# BackUp_uC.net
KiCad netlist of a schematic drawn in Altium Designer
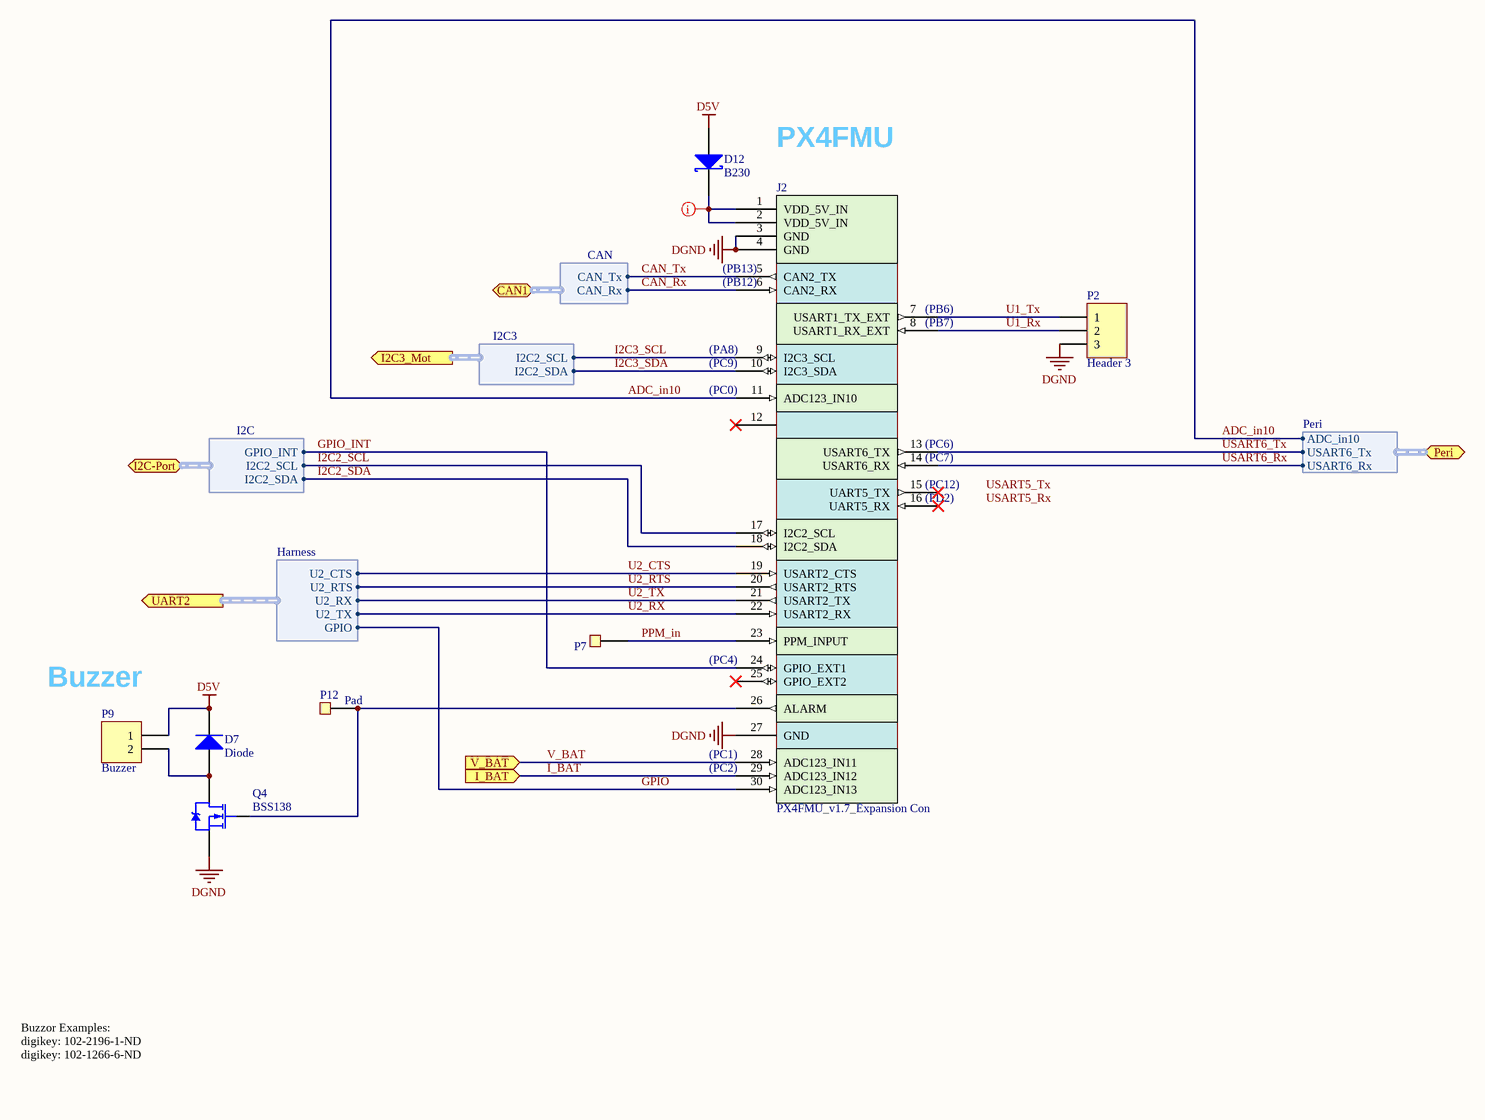
[diagram p0: BackUp_uC.SchDoc]

(export (version "E")
  (design (tool "Eeschema 10.0.6"))
  (components
    (comp (ref "D7")
      (value "Diode")
      (footprint "Mini MELF - SOD-80 -N")
      (description "Default Diode")
      (libsource (lib "IDSC std generic parts ") (part "Diode"))
    )
    (comp (ref "D12")
      (value "B230")
      (footprint "Diode SMB DO-214aa -N")
      (description "Schottky Diode")
      (libsource (lib "IDSC std generic parts ") (part "Diode  Schottky"))
    )
    (comp (ref "J2")
      (value "PX4FMU_v1.7_Expansion Con")
      (footprint "PX4FMU_v1.7_module_sicket")
      (description "J2 / J3")
      (libsource (lib "IDSC_PX4_modules") (part "PX4FMU_v1.7_Expansion Con_1"))
    )
    (comp (ref "P2")
      (value "Header 3")
      (footprint "HDR1X3")
      (description "Header, 3-Pin")
      (libsource (lib "IDSC std connectors") (part "Header 3"))
    )
    (comp (ref "P7")
      (value "Pad")
      (footprint "PIN1 style 2")
      (description "Single Pad or Testpoint")
      (libsource (lib "IDSC std connectors") (part "Pad"))
    )
    (comp (ref "P9")
      (value "Buzzer")
      (footprint "HDR1X2")
      (description "Header, 2-Pin")
      (libsource (lib "IDSC std connectors") (part "Header 2"))
    )
    (comp (ref "P12")
      (value "Pad")
      (footprint "Pad_0603")
      (description "Single Pad or Testpoint")
      (libsource (lib "IDSC std connectors") (part "Pad"))
    )
    (comp (ref "Q4")
      (value "BSS138")
      (footprint "SOT23-N")
      (description "N-Channel MOSFET")
      (libsource (lib "IDSC std generic parts ") (part "MOSFET-N2"))
    )
  )
  (nets
    (net (code "6") (name "/ADC_in10") (class "Default")
      (node (ref "J2") (pin "11") (pinfunction "ADC123_IN10_11") (pintype "input"))
    )
    (net (code "7") (name "/CAN_Rx") (class "Default")
      (node (ref "J2") (pin "6") (pinfunction "CAN2_RX_6") (pintype "input"))
    )
    (net (code "8") (name "/CAN_Tx") (class "Default")
      (node (ref "J2") (pin "5") (pinfunction "CAN2_TX_5") (pintype "output"))
    )
    (net (code "9") (name "/GPIO") (class "Default")
      (node (ref "J2") (pin "30") (pinfunction "ADC123_IN13_30") (pintype "input"))
    )
    (net (code "10") (name "/GPIO_INT") (class "Default")
      (node (ref "J2") (pin "24") (pinfunction "GPIO_EXT1_24") (pintype "bidirectional"))
    )
    (net (code "11") (name "/I2C2_SCL") (class "Default")
      (node (ref "J2") (pin "17") (pinfunction "I2C2_SCL_17") (pintype "bidirectional"))
    )
    (net (code "12") (name "/I2C2_SDA") (class "Default")
      (node (ref "J2") (pin "18") (pinfunction "I2C2_SDA_18") (pintype "bidirectional"))
    )
    (net (code "13") (name "/I2C3_SCL") (class "Default")
      (node (ref "J2") (pin "9") (pinfunction "I2C3_SCL_9") (pintype "bidirectional"))
    )
    (net (code "14") (name "/I2C3_SDA") (class "Default")
      (node (ref "J2") (pin "10") (pinfunction "I2C3_SDA_10") (pintype "bidirectional"))
    )
    (net (code "15") (name "/I_BAT") (class "Default")
      (node (ref "J2") (pin "29") (pinfunction "ADC123_IN12_29") (pintype "input"))
    )
    (net (code "16") (name "/PPM_in") (class "Default")
      (node (ref "J2") (pin "23") (pinfunction "PPM_INPUT_23") (pintype "input"))
      (node (ref "P7") (pin "1") (pinfunction "1_1") (pintype "passive"))
    )
    (net (code "17") (name "/U1_Rx") (class "Default")
      (node (ref "J2") (pin "8") (pinfunction "USART1_RX_EXT_8") (pintype "input"))
      (node (ref "P2") (pin "2") (pinfunction "2_2") (pintype "passive"))
    )
    (net (code "18") (name "/U1_Tx") (class "Default")
      (node (ref "J2") (pin "7") (pinfunction "USART1_TX_EXT_7") (pintype "output"))
      (node (ref "P2") (pin "1") (pinfunction "1_1") (pintype "passive"))
    )
    (net (code "19") (name "/U2_CTS") (class "Default")
      (node (ref "J2") (pin "19") (pinfunction "USART2_CTS_19") (pintype "input"))
    )
    (net (code "20") (name "/U2_RTS") (class "Default")
      (node (ref "J2") (pin "20") (pinfunction "USART2_RTS_20") (pintype "output"))
    )
    (net (code "21") (name "/U2_RX") (class "Default")
      (node (ref "J2") (pin "22") (pinfunction "USART2_RX_22") (pintype "input"))
    )
    (net (code "22") (name "/U2_TX") (class "Default")
      (node (ref "J2") (pin "21") (pinfunction "USART2_TX_21") (pintype "output"))
    )
    (net (code "25") (name "/USART6_Rx") (class "Default")
      (node (ref "J2") (pin "14") (pinfunction "USART6_RX_14") (pintype "input"))
    )
    (net (code "26") (name "/USART6_Tx") (class "Default")
      (node (ref "J2") (pin "13") (pinfunction "USART6_TX_13") (pintype "output"))
    )
    (net (code "27") (name "/V_BAT") (class "Default")
      (node (ref "J2") (pin "28") (pinfunction "ADC123_IN11_28") (pintype "input"))
    )
    (net (code "33") (name "D5V") (class "Default")
      (node (ref "D12") (pin "1") (pinfunction "A_1") (pintype "passive"))
      (node (ref "D7") (pin "2") (pinfunction "K_2") (pintype "passive"))
      (node (ref "P9") (pin "1") (pinfunction "1_1") (pintype "passive"))
    )
    (net (code "34") (name "DGND") (class "Default")
      (node (ref "J2") (pin "27") (pinfunction "GND_27") (pintype "power_in"))
      (node (ref "J2") (pin "3") (pinfunction "GND_3") (pintype "power_in"))
      (node (ref "J2") (pin "4") (pinfunction "GND_4") (pintype "power_in"))
      (node (ref "P2") (pin "3") (pinfunction "3_3") (pintype "passive"))
      (node (ref "Q4") (pin "2") (pinfunction "S_2") (pintype "passive"))
    )
    (net (code "35") (name "Net-(D7-A)") (class "Default")
      (node (ref "D7") (pin "1") (pinfunction "A_1") (pintype "passive"))
      (node (ref "P9") (pin "2") (pinfunction "2_2") (pintype "passive"))
      (node (ref "Q4") (pin "3") (pinfunction "D_3") (pintype "passive"))
    )
    (net (code "36") (name "Net-(D12-K)") (class "Default")
      (node (ref "D12") (pin "2") (pinfunction "K_2") (pintype "passive"))
      (node (ref "J2") (pin "1") (pinfunction "VDD_5V_IN_1") (pintype "power_in"))
      (node (ref "J2") (pin "2") (pinfunction "VDD_5V_IN_2") (pintype "power_in"))
    )
    (net (code "37") (name "Net-(J2-ALARM)") (class "Default")
      (node (ref "J2") (pin "26") (pinfunction "ALARM_26") (pintype "output"))
      (node (ref "P12") (pin "1") (pinfunction "1_1") (pintype "passive"))
      (node (ref "Q4") (pin "1") (pinfunction "G_1") (pintype "passive"))
    )
    (net (code "38") (name "unconnected-(J2-GPIO_EXT2-Pad25)") (class "Default")
      (node (ref "J2") (pin "25") (pinfunction "GPIO_EXT2_25") (pintype "bidirectional+no_connect"))
    )
    (net (code "39") (name "unconnected-(J2-Pad12)") (class "Default")
      (node (ref "J2") (pin "12") (pintype "passive+no_connect"))
    )
    (net (code "40") (name "unconnected-(J2-UART5_RX-Pad16)") (class "Default")
      (node (ref "J2") (pin "16") (pinfunction "UART5_RX_16") (pintype "input+no_connect"))
    )
    (net (code "41") (name "unconnected-(J2-UART5_TX-Pad15)") (class "Default")
      (node (ref "J2") (pin "15") (pinfunction "UART5_TX_15") (pintype "output+no_connect"))
    )
  )
)
